# BMS_Slave_Rev2.net
KiCad netlist of a schematic drawn in Altium Designer
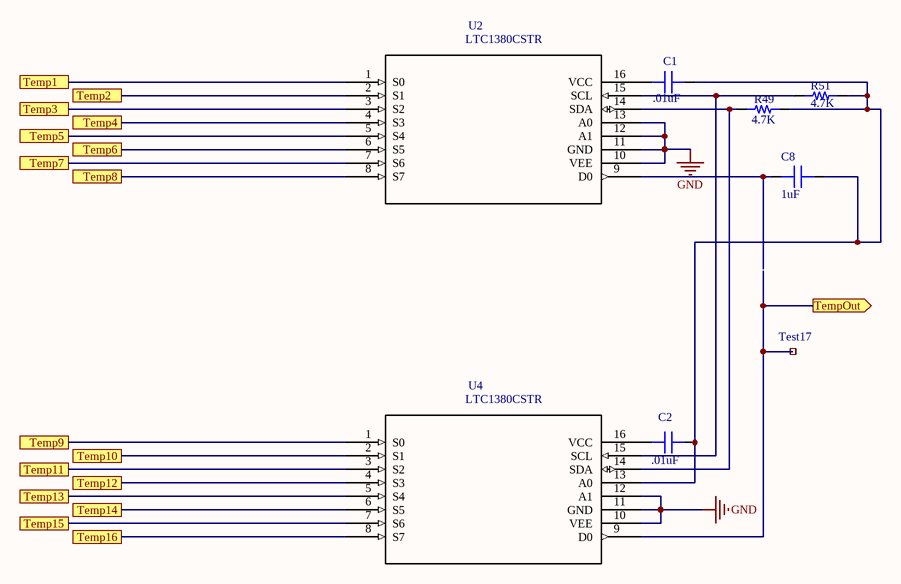
[diagram p0: BMS_Slave_Rev2.SchDoc]

(export (version "E")
  (design (tool "Eeschema 10.0.6"))
  (components
    (comp (ref "C1")
      (value "capacitor")
      (footprint "0603")
      (description "Generic 0603 capacitor")
      (fields (field (name "CAPACITANCE") ".01uF") (field (name "VOLTAGE") "50"))
      (libsource (lib "altlib") (part "capacitor"))
    )
    (comp (ref "C2")
      (value "capacitor")
      (footprint "0603")
      (description "Generic 0603 capacitor")
      (fields (field (name "CAPACITANCE") ".01uF") (field (name "VOLTAGE") "50"))
      (libsource (lib "altlib") (part "capacitor"))
    )
    (comp (ref "C8")
      (value "capacitor")
      (footprint "0603")
      (description "Generic 0603 capacitor")
      (fields (field (name "CAPACITANCE") "1uF") (field (name "VOLTAGE") "50"))
      (libsource (lib "altlib") (part "capacitor"))
    )
    (comp (ref "R49")
      (value "resistor")
      (footprint "0603")
      (fields (field (name "RESISTANCE") "4.7K"))
      (libsource (lib "altlib") (part "resistor"))
    )
    (comp (ref "R51")
      (value "resistor")
      (footprint "0603")
      (fields (field (name "RESISTANCE") "4.7K"))
      (libsource (lib "altlib") (part "resistor"))
    )
    (comp (ref "Test17") (value "RCU-0C") (footprint "RCU-0C") (libsource (lib "altlib") (part "RCU-0C")))
    (comp (ref "U2")
      (value "LTC1380CSTR")
      (footprint "SO-16_S")
      (description "LTC1380 - Single-Ended 8-Channel/ Differential 4-Channel Analog Multiplexer with SMBus Interface")
      (fields (field (name "MF") "Linear Technology") (field (name "MP") "LTC1380CS#TR"))
      (libsource (lib "LTC1380CSTR") (part "LTC1380CSTR"))
    )
    (comp (ref "U4")
      (value "LTC1380CSTR")
      (footprint "SO-16_S")
      (description "LTC1380 - Single-Ended 8-Channel/ Differential 4-Channel Analog Multiplexer with SMBus Interface")
      (fields (field (name "MF") "Linear Technology") (field (name "MP") "LTC1380CS#TR"))
      (libsource (lib "LTC1380CSTR") (part "LTC1380CSTR"))
    )
  )
  (nets
    (net (code "1") (name "/Temp1") (class "Default")
      (node (ref "U2") (pin "1") (pinfunction "S0_1") (pintype "input"))
    )
    (net (code "2") (name "/Temp2") (class "Default")
      (node (ref "U2") (pin "2") (pinfunction "S1_2") (pintype "input"))
    )
    (net (code "3") (name "/Temp3") (class "Default")
      (node (ref "U2") (pin "3") (pinfunction "S2_3") (pintype "input"))
    )
    (net (code "4") (name "/Temp4") (class "Default")
      (node (ref "U2") (pin "4") (pinfunction "S3_4") (pintype "input"))
    )
    (net (code "5") (name "/Temp5") (class "Default")
      (node (ref "U2") (pin "5") (pinfunction "S4_5") (pintype "input"))
    )
    (net (code "6") (name "/Temp6") (class "Default")
      (node (ref "U2") (pin "6") (pinfunction "S5_6") (pintype "input"))
    )
    (net (code "7") (name "/Temp7") (class "Default")
      (node (ref "U2") (pin "7") (pinfunction "S6_7") (pintype "input"))
    )
    (net (code "8") (name "/Temp8") (class "Default")
      (node (ref "U2") (pin "8") (pinfunction "S7_8") (pintype "input"))
    )
    (net (code "9") (name "/Temp9") (class "Default")
      (node (ref "U4") (pin "1") (pinfunction "S0_1") (pintype "input"))
    )
    (net (code "10") (name "/Temp10") (class "Default")
      (node (ref "U4") (pin "2") (pinfunction "S1_2") (pintype "input"))
    )
    (net (code "11") (name "/Temp11") (class "Default")
      (node (ref "U4") (pin "3") (pinfunction "S2_3") (pintype "input"))
    )
    (net (code "12") (name "/Temp12") (class "Default")
      (node (ref "U4") (pin "4") (pinfunction "S3_4") (pintype "input"))
    )
    (net (code "13") (name "/Temp13") (class "Default")
      (node (ref "U4") (pin "5") (pinfunction "S4_5") (pintype "input"))
    )
    (net (code "14") (name "/Temp14") (class "Default")
      (node (ref "U4") (pin "6") (pinfunction "S5_6") (pintype "input"))
    )
    (net (code "15") (name "/Temp15") (class "Default")
      (node (ref "U4") (pin "7") (pinfunction "S6_7") (pintype "input"))
    )
    (net (code "16") (name "/Temp16") (class "Default")
      (node (ref "U4") (pin "8") (pinfunction "S7_8") (pintype "input"))
    )
    (net (code "17") (name "/TempOut") (class "Default")
      (node (ref "Test17") (pin "1") (pintype "passive"))
      (node (ref "U4") (pin "9") (pinfunction "D0_9") (pintype "output"))
    )
    (net (code "18") (name "GND") (class "Default")
      (node (ref "U2") (pin "10") (pinfunction "VEE_10") (pintype "power_in"))
      (node (ref "U2") (pin "11") (pinfunction "GND_11") (pintype "power_in"))
      (node (ref "U2") (pin "12") (pinfunction "A1_12") (pintype "passive"))
      (node (ref "U2") (pin "13") (pinfunction "A0_13") (pintype "passive"))
      (node (ref "U4") (pin "10") (pinfunction "VEE_10") (pintype "power_in"))
      (node (ref "U4") (pin "11") (pinfunction "GND_11") (pintype "power_in"))
      (node (ref "U4") (pin "12") (pinfunction "A1_12") (pintype "passive"))
    )
    (net (code "19") (name "Net-(U2-D0)") (class "Default")
      (node (ref "C8") (pin "1") (pinfunction "1_1") (pintype "passive"))
      (node (ref "U2") (pin "9") (pinfunction "D0_9") (pintype "output"))
    )
    (net (code "20") (name "Net-(U2-SCL)") (class "Default")
      (node (ref "R51") (pin "1") (pinfunction "1_1") (pintype "passive"))
      (node (ref "U2") (pin "15") (pinfunction "SCL_15") (pintype "input"))
      (node (ref "U4") (pin "15") (pinfunction "SCL_15") (pintype "input"))
    )
    (net (code "21") (name "Net-(U2-SDA)") (class "Default")
      (node (ref "R49") (pin "1") (pinfunction "1_1") (pintype "passive"))
      (node (ref "U2") (pin "14") (pinfunction "SDA_14") (pintype "bidirectional"))
      (node (ref "U4") (pin "14") (pinfunction "SDA_14") (pintype "bidirectional"))
    )
    (net (code "22") (name "Net-(U2-VCC)") (class "Default")
      (node (ref "C1") (pin "1") (pinfunction "1_1") (pintype "passive"))
      (node (ref "U2") (pin "16") (pinfunction "VCC_16") (pintype "power_in"))
    )
    (net (code "23") (name "Net-(U4-A0)") (class "Default")
      (node (ref "C1") (pin "2") (pinfunction "2_2") (pintype "passive"))
      (node (ref "C2") (pin "2") (pinfunction "2_2") (pintype "passive"))
      (node (ref "C8") (pin "2") (pinfunction "2_2") (pintype "passive"))
      (node (ref "R49") (pin "2") (pinfunction "2_2") (pintype "passive"))
      (node (ref "R51") (pin "2") (pinfunction "2_2") (pintype "passive"))
      (node (ref "U4") (pin "13") (pinfunction "A0_13") (pintype "passive"))
    )
    (net (code "24") (name "Net-(U4-VCC)") (class "Default")
      (node (ref "C2") (pin "1") (pinfunction "1_1") (pintype "passive"))
      (node (ref "U4") (pin "16") (pinfunction "VCC_16") (pintype "power_in"))
    )
  )
)
